# AJH_Wasp_1_02.net
KiCad netlist of a schematic drawn in EAGLE
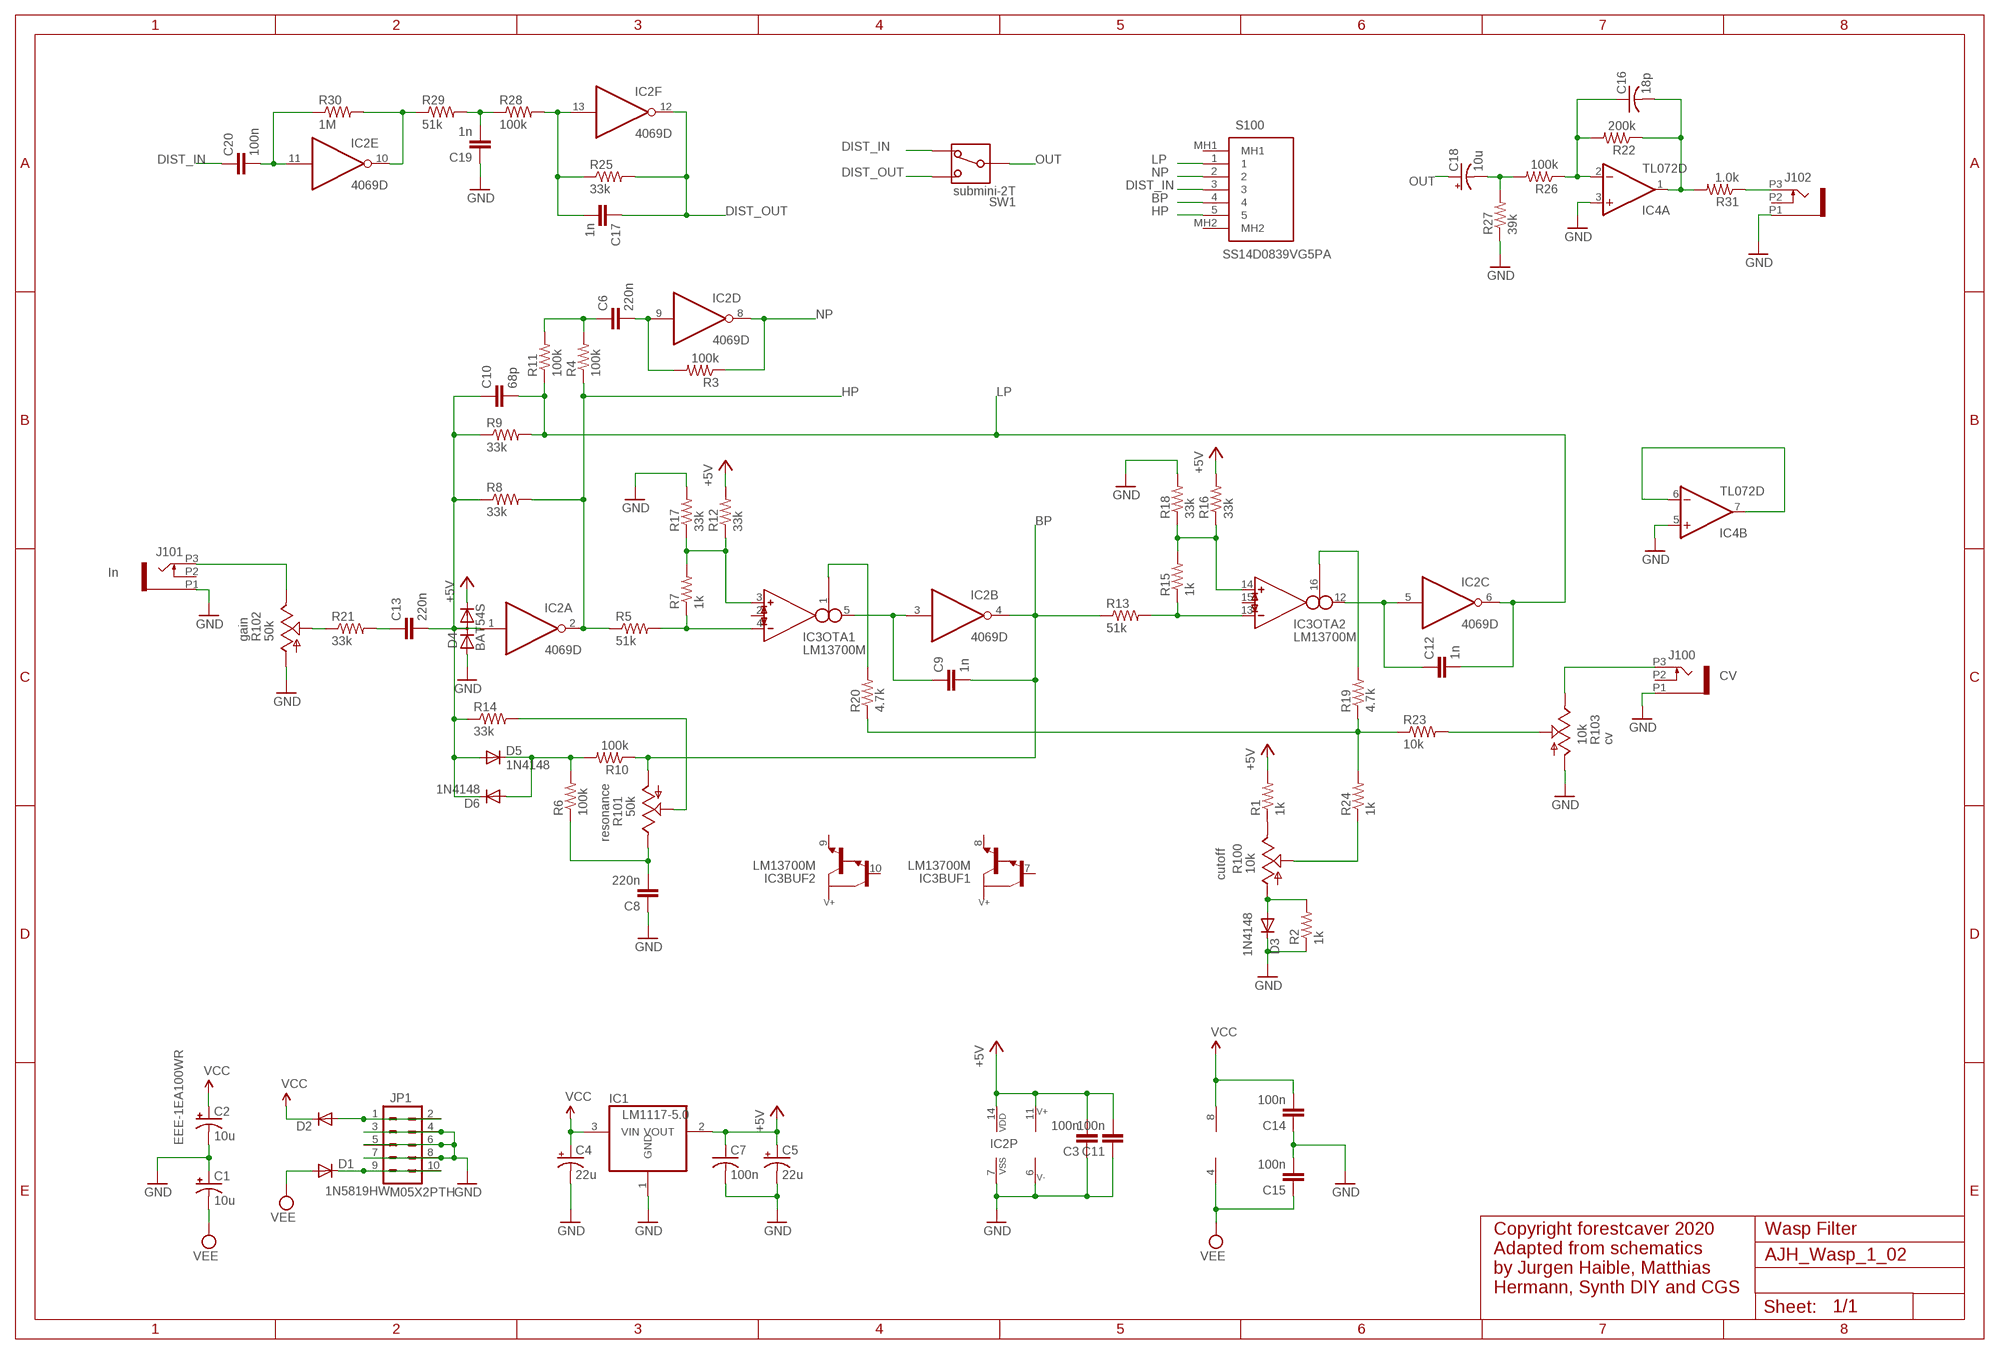
[diagram p0: schematic, sheet 1]

(export (version "E")
  (design (tool "Eeschema 10.0.6"))
  (components
    (comp (ref "C1")
      (value "10u")
      (footprint "eagle-import:PANASONIC_B")
      (libsource (lib "eagle-import") (part "CPOL-USB"))
    )
    (comp (ref "C2")
      (value "10u")
      (footprint "eagle-import:PANASONIC_B")
      (libsource (lib "eagle-import") (part "CPOL-USB"))
    )
    (comp (ref "C3")
      (value "100n")
      (footprint "eagle-import:C0603")
      (libsource (lib "eagle-import") (part "C-EUC0603"))
    )
    (comp (ref "C4")
      (value "22u")
      (footprint "eagle-import:PANASONIC_C")
      (libsource (lib "eagle-import") (part "CPOL-USC"))
    )
    (comp (ref "C5")
      (value "22u")
      (footprint "eagle-import:PANASONIC_C")
      (libsource (lib "eagle-import") (part "CPOL-USC"))
    )
    (comp (ref "C6")
      (value "220n")
      (footprint "eagle-import:C0603")
      (libsource (lib "eagle-import") (part "C-EUC0603"))
    )
    (comp (ref "C7")
      (value "100n")
      (footprint "eagle-import:C0603")
      (libsource (lib "eagle-import") (part "C-USC0603"))
    )
    (comp (ref "C8")
      (value "220n")
      (footprint "eagle-import:C0603")
      (libsource (lib "eagle-import") (part "C-EUC0603"))
    )
    (comp (ref "C9")
      (value "1n")
      (footprint "eagle-import:C0603")
      (libsource (lib "eagle-import") (part "C-EUC0603"))
    )
    (comp (ref "C10")
      (value "68p")
      (footprint "eagle-import:C0603")
      (libsource (lib "eagle-import") (part "C-EUC0603"))
    )
    (comp (ref "C11")
      (value "100n")
      (footprint "eagle-import:C0603")
      (libsource (lib "eagle-import") (part "C-EUC0603"))
    )
    (comp (ref "C12")
      (value "1n")
      (footprint "eagle-import:C0603")
      (libsource (lib "eagle-import") (part "C-EUC0603"))
    )
    (comp (ref "C13")
      (value "220n")
      (footprint "eagle-import:C0603")
      (libsource (lib "eagle-import") (part "C-EUC0603"))
    )
    (comp (ref "C14")
      (value "100n")
      (footprint "eagle-import:C0603")
      (libsource (lib "eagle-import") (part "C-EUC0603"))
    )
    (comp (ref "C15")
      (value "100n")
      (footprint "eagle-import:C0603")
      (libsource (lib "eagle-import") (part "C-EUC0603"))
    )
    (comp (ref "C16")
      (value "18p")
      (footprint "eagle-import:C0603")
      (libsource (lib "eagle-import") (part "C-USC0603"))
    )
    (comp (ref "C17")
      (value "1n")
      (footprint "eagle-import:C0603")
      (libsource (lib "eagle-import") (part "C-EUC0603"))
    )
    (comp (ref "C18")
      (value "10u")
      (footprint "eagle-import:PANASONIC_B")
      (libsource (lib "eagle-import") (part "CPOL-USB"))
    )
    (comp (ref "C19")
      (value "1n")
      (footprint "eagle-import:C0603")
      (libsource (lib "eagle-import") (part "C-EUC0603"))
    )
    (comp (ref "C20")
      (value "100n")
      (footprint "eagle-import:C0603")
      (libsource (lib "eagle-import") (part "C-EUC0603"))
    )
    (comp (ref "D1")
      (value "1N5819HW")
      (footprint "eagle-import:SOD123")
      (libsource (lib "eagle-import") (part "DIODE-SOD123"))
    )
    (comp (ref "D2")
      (value "1N5819HW")
      (footprint "eagle-import:SOD123")
      (libsource (lib "eagle-import") (part "DIODE-SOD123"))
    )
    (comp (ref "D3")
      (value "1N4148")
      (footprint "eagle-import:SOD523")
      (libsource (lib "eagle-import") (part "DIODE-SOD523"))
    )
    (comp (ref "D4")
      (value "BAT54S")
      (footprint "eagle-import:SOT23")
      (libsource (lib "eagle-import") (part "DIODE_2CACA-SOT23"))
    )
    (comp (ref "D5")
      (value "1N4148")
      (footprint "eagle-import:SOD523")
      (libsource (lib "eagle-import") (part "DIODE-SOD523"))
    )
    (comp (ref "D6")
      (value "1N4148")
      (footprint "eagle-import:SOD523")
      (libsource (lib "eagle-import") (part "DIODE-SOD523"))
    )
    (comp (ref "IC1")
      (value "LM1117-5.0")
      (footprint "eagle-import:SOT223")
      (libsource (lib "eagle-import") (part "REG1117"))
    )
    (comp (ref "IC2")
      (value "4069D")
      (footprint "eagle-import:SO14")
      (libsource (lib "eagle-import") (part "4069D"))
    )
    (comp (ref "IC3")
      (value "LM13700M")
      (footprint "eagle-import:SO16")
      (libsource (lib "eagle-import") (part "LM13700M"))
    )
    (comp (ref "IC4")
      (value "TL072D")
      (footprint "eagle-import:SO08")
      (libsource (lib "eagle-import") (part "TL072D"))
    )
    (comp (ref "J100")
      (value "PJ301_THONKICONN8")
      (footprint "eagle-import:WQP_PJ_301M8")
      (fields (field (name "LABEL") "CV"))
      (libsource (lib "eagle-import") (part "PJ301_THONKICONN8"))
    )
    (comp (ref "J101")
      (value "PJ301_THONKICONN8")
      (footprint "eagle-import:WQP_PJ_301M8")
      (fields (field (name "LABEL") "In"))
      (libsource (lib "eagle-import") (part "PJ301_THONKICONN8"))
    )
    (comp (ref "J102")
      (value "PJ301_THONKICONN6")
      (footprint "eagle-import:WQP_PJ_301M6")
      (libsource (lib "eagle-import") (part "PJ301_THONKICONN6"))
    )
    (comp (ref "JP1")
      (value "M05X2PTH")
      (footprint "eagle-import:AVR_ICSP")
      (libsource (lib "eagle-import") (part "M05X2PTH"))
    )
    (comp (ref "R1")
      (value "1k")
      (footprint "eagle-import:R0603")
      (libsource (lib "eagle-import") (part "rcl_334_R-US_R0603"))
    )
    (comp (ref "R2")
      (value "1k")
      (footprint "eagle-import:R0603")
      (libsource (lib "eagle-import") (part "rcl_334_R-US_R0603"))
    )
    (comp (ref "R3")
      (value "100k")
      (footprint "eagle-import:R0603")
      (libsource (lib "eagle-import") (part "rcl_334_R-US_R0603"))
    )
    (comp (ref "R4")
      (value "100k")
      (footprint "eagle-import:R0603")
      (libsource (lib "eagle-import") (part "rcl_334_R-US_R0603"))
    )
    (comp (ref "R5")
      (value "51k")
      (footprint "eagle-import:R0603")
      (libsource (lib "eagle-import") (part "rcl_334_R-US_R0603"))
    )
    (comp (ref "R6")
      (value "100k")
      (footprint "eagle-import:R0603")
      (libsource (lib "eagle-import") (part "rcl_334_R-US_R0603"))
    )
    (comp (ref "R7")
      (value "1k")
      (footprint "eagle-import:R0603")
      (libsource (lib "eagle-import") (part "rcl_334_R-US_R0603"))
    )
    (comp (ref "R8")
      (value "33k")
      (footprint "eagle-import:R0603")
      (libsource (lib "eagle-import") (part "rcl_334_R-US_R0603"))
    )
    (comp (ref "R9")
      (value "33k")
      (footprint "eagle-import:R0603")
      (libsource (lib "eagle-import") (part "rcl_334_R-US_R0603"))
    )
    (comp (ref "R10")
      (value "100k")
      (footprint "eagle-import:R0603")
      (libsource (lib "eagle-import") (part "rcl_334_R-US_R0603"))
    )
    (comp (ref "R11")
      (value "100k")
      (footprint "eagle-import:R0603")
      (libsource (lib "eagle-import") (part "rcl_334_R-US_R0603"))
    )
    (comp (ref "R12")
      (value "33k")
      (footprint "eagle-import:R0603")
      (libsource (lib "eagle-import") (part "rcl_334_R-US_R0603"))
    )
    (comp (ref "R13")
      (value "51k")
      (footprint "eagle-import:R0603")
      (libsource (lib "eagle-import") (part "rcl_334_R-US_R0603"))
    )
    (comp (ref "R14")
      (value "33k")
      (footprint "eagle-import:R0603")
      (libsource (lib "eagle-import") (part "rcl_334_R-US_R0603"))
    )
    (comp (ref "R15")
      (value "1k")
      (footprint "eagle-import:R0603")
      (libsource (lib "eagle-import") (part "rcl_334_R-US_R0603"))
    )
    (comp (ref "R16")
      (value "33k")
      (footprint "eagle-import:R0603")
      (libsource (lib "eagle-import") (part "rcl_334_R-US_R0603"))
    )
    (comp (ref "R17")
      (value "33k")
      (footprint "eagle-import:R0603")
      (libsource (lib "eagle-import") (part "rcl_334_R-US_R0603"))
    )
    (comp (ref "R18")
      (value "33k")
      (footprint "eagle-import:R0603")
      (libsource (lib "eagle-import") (part "rcl_334_R-US_R0603"))
    )
    (comp (ref "R19")
      (value "4.7k")
      (footprint "eagle-import:R0603")
      (libsource (lib "eagle-import") (part "rcl_334_R-US_R0603"))
    )
    (comp (ref "R20")
      (value "4.7k")
      (footprint "eagle-import:R0603")
      (libsource (lib "eagle-import") (part "rcl_334_R-US_R0603"))
    )
    (comp (ref "R21")
      (value "33k")
      (footprint "eagle-import:R0603")
      (libsource (lib "eagle-import") (part "rcl_334_R-US_R0603"))
    )
    (comp (ref "R22")
      (value "200k")
      (footprint "eagle-import:R0603")
      (libsource (lib "eagle-import") (part "R-US_R0603"))
    )
    (comp (ref "R23")
      (value "10k")
      (footprint "eagle-import:R0603")
      (libsource (lib "eagle-import") (part "rcl_334_R-US_R0603"))
    )
    (comp (ref "R24")
      (value "1k")
      (footprint "eagle-import:R0603")
      (libsource (lib "eagle-import") (part "rcl_334_R-US_R0603"))
    )
    (comp (ref "R25")
      (value "33k")
      (footprint "eagle-import:R0603")
      (libsource (lib "eagle-import") (part "rcl_334_R-US_R0603"))
    )
    (comp (ref "R26")
      (value "100k")
      (footprint "eagle-import:R0603")
      (libsource (lib "eagle-import") (part "R-US_R0603"))
    )
    (comp (ref "R27")
      (value "39k")
      (footprint "eagle-import:R0603")
      (libsource (lib "eagle-import") (part "R-US_R0603"))
    )
    (comp (ref "R28")
      (value "100k")
      (footprint "eagle-import:R0603")
      (libsource (lib "eagle-import") (part "rcl_334_R-US_R0603"))
    )
    (comp (ref "R29")
      (value "51k")
      (footprint "eagle-import:R0603")
      (libsource (lib "eagle-import") (part "rcl_334_R-US_R0603"))
    )
    (comp (ref "R30")
      (value "1M")
      (footprint "eagle-import:R0603")
      (libsource (lib "eagle-import") (part "rcl_334_R-US_R0603"))
    )
    (comp (ref "R31")
      (value "1.0k")
      (footprint "eagle-import:R0603")
      (libsource (lib "eagle-import") (part "R-US_R0603"))
    )
    (comp (ref "R100")
      (value "10k")
      (footprint "eagle-import:ALPS_POT_VERTICAL_PS")
      (fields (field (name "LABEL") "cutoff"))
      (libsource (lib "eagle-import") (part "POT_USVERTICAL_PS"))
    )
    (comp (ref "R101")
      (value "50k")
      (footprint "eagle-import:ALPS_POT_VERTICAL_PS")
      (fields (field (name "LABEL") "resonance"))
      (libsource (lib "eagle-import") (part "POT_USVERTICAL_PS"))
    )
    (comp (ref "R102")
      (value "50k")
      (footprint "eagle-import:ALPS_POT_VERTICAL_PS")
      (fields (field (name "LABEL") "gain"))
      (libsource (lib "eagle-import") (part "POT_USVERTICAL_PS"))
    )
    (comp (ref "R103")
      (value "10k")
      (footprint "eagle-import:ALPS_POT_VERTICAL_PS")
      (fields (field (name "LABEL") "cv"))
      (libsource (lib "eagle-import") (part "POT_USVERTICAL_PS"))
    )
    (comp (ref "S100")
      (value "SS14D0839VG5PA")
      (footprint "eagle-import:SS14D0839VG5PA")
      (fields (field (name "MOUSER_PART_NUMBER") "611-SS-14D0839-VG5PA"))
      (libsource (lib "eagle-import") (part "SS14D0839VG5PA"))
    )
    (comp (ref "SW1")
      (value "submini-2T")
      (footprint "eagle-import:SPDT-SUB")
      (libsource (lib "eagle-import") (part "SPDTT"))
    )
  )
  (nets
    (net (code "1") (name "+5V") (class "Default")
      (node (ref "C11") (pin "2") (pinfunction "2_2") (pintype "passive"))
      (node (ref "C3") (pin "2") (pinfunction "2_2") (pintype "passive"))
      (node (ref "C5") (pin "+") (pinfunction "+_+") (pintype "passive"))
      (node (ref "C7") (pin "1") (pinfunction "1_1") (pintype "passive"))
      (node (ref "D4") (pin "2") (pinfunction "C_2") (pintype "passive"))
      (node (ref "IC1") (pin "2") (pinfunction "VOUT_2") (pintype "output"))
      (node (ref "IC2") (pin "14") (pinfunction "VDD_14") (pintype "power_in"))
      (node (ref "IC3") (pin "11") (pinfunction "V+_11") (pintype "power_in"))
      (node (ref "R1") (pin "2") (pinfunction "2_2") (pintype "passive"))
      (node (ref "R12") (pin "2") (pinfunction "2_2") (pintype "passive"))
      (node (ref "R16") (pin "2") (pinfunction "2_2") (pintype "passive"))
    )
    (net (code "2") (name "/BP") (class "Default")
      (node (ref "C9") (pin "2") (pinfunction "2_2") (pintype "passive"))
      (node (ref "IC2") (pin "4") (pinfunction "O_4") (pintype "output"))
      (node (ref "R10") (pin "1") (pinfunction "1_1") (pintype "passive"))
      (node (ref "R101") (pin "P$3") (pinfunction "A_P$3") (pintype "passive"))
      (node (ref "R13") (pin "1") (pinfunction "1_1") (pintype "passive"))
      (node (ref "S100") (pin "4") (pinfunction "4_4") (pintype "bidirectional"))
    )
    (net (code "3") (name "/DIST_IN") (class "Default")
      (node (ref "C20") (pin "1") (pinfunction "1_1") (pintype "passive"))
      (node (ref "S100") (pin "3") (pinfunction "3_3") (pintype "bidirectional"))
      (node (ref "SW1") (pin "P$3") (pinfunction "P$3_P$3") (pintype "passive"))
    )
    (net (code "4") (name "/DIST_OUT") (class "Default")
      (node (ref "C17") (pin "1") (pinfunction "1_1") (pintype "passive"))
      (node (ref "IC2") (pin "12") (pinfunction "O_12") (pintype "output"))
      (node (ref "R25") (pin "2") (pinfunction "2_2") (pintype "passive"))
      (node (ref "SW1") (pin "P$1") (pinfunction "P$1_P$1") (pintype "passive"))
    )
    (net (code "5") (name "/HP") (class "Default")
      (node (ref "IC2") (pin "2") (pinfunction "O_2") (pintype "output"))
      (node (ref "R4") (pin "1") (pinfunction "1_1") (pintype "passive"))
      (node (ref "R5") (pin "1") (pinfunction "1_1") (pintype "passive"))
      (node (ref "R8") (pin "2") (pinfunction "2_2") (pintype "passive"))
      (node (ref "S100") (pin "5") (pinfunction "5_5") (pintype "bidirectional"))
    )
    (net (code "6") (name "/LP") (class "Default")
      (node (ref "C10") (pin "2") (pinfunction "2_2") (pintype "passive"))
      (node (ref "C12") (pin "2") (pinfunction "2_2") (pintype "passive"))
      (node (ref "IC2") (pin "6") (pinfunction "O_6") (pintype "output"))
      (node (ref "R11") (pin "1") (pinfunction "1_1") (pintype "passive"))
      (node (ref "R9") (pin "2") (pinfunction "2_2") (pintype "passive"))
      (node (ref "S100") (pin "1") (pinfunction "1_1") (pintype "bidirectional"))
    )
    (net (code "7") (name "/NP") (class "Default")
      (node (ref "IC2") (pin "8") (pinfunction "O_8") (pintype "output"))
      (node (ref "R3") (pin "1") (pinfunction "1_1") (pintype "passive"))
      (node (ref "S100") (pin "2") (pinfunction "2_2") (pintype "bidirectional"))
    )
    (net (code "8") (name "/OUT") (class "Default")
      (node (ref "C18") (pin "+") (pinfunction "+_+") (pintype "passive"))
      (node (ref "SW1") (pin "P$2") (pinfunction "P$2_P$2") (pintype "passive"))
    )
    (net (code "9") (name "GND") (class "Default")
      (node (ref "C1") (pin "+") (pinfunction "+_+") (pintype "passive"))
      (node (ref "C11") (pin "1") (pinfunction "1_1") (pintype "passive"))
      (node (ref "C14") (pin "1") (pinfunction "1_1") (pintype "passive"))
      (node (ref "C15") (pin "2") (pinfunction "2_2") (pintype "passive"))
      (node (ref "C19") (pin "1") (pinfunction "1_1") (pintype "passive"))
      (node (ref "C2") (pin "-") (pinfunction "-_-") (pintype "passive"))
      (node (ref "C3") (pin "1") (pinfunction "1_1") (pintype "passive"))
      (node (ref "C4") (pin "-") (pinfunction "-_-") (pintype "passive"))
      (node (ref "C5") (pin "-") (pinfunction "-_-") (pintype "passive"))
      (node (ref "C7") (pin "2") (pinfunction "2_2") (pintype "passive"))
      (node (ref "C8") (pin "1") (pinfunction "1_1") (pintype "passive"))
      (node (ref "D3") (pin "C") (pinfunction "C_C") (pintype "passive"))
      (node (ref "D4") (pin "1") (pinfunction "A_1") (pintype "passive"))
      (node (ref "IC1") (pin "1") (pinfunction "GND_1") (pintype "power_in"))
      (node (ref "IC2") (pin "7") (pinfunction "VSS_7") (pintype "power_in"))
      (node (ref "IC3") (pin "6") (pinfunction "V-_6") (pintype "power_in"))
      (node (ref "IC4") (pin "3") (pinfunction "+IN_3") (pintype "input"))
      (node (ref "IC4") (pin "5") (pinfunction "+IN_5") (pintype "input"))
      (node (ref "J100") (pin "P1") (pinfunction "1_P1") (pintype "passive"))
      (node (ref "J101") (pin "P1") (pinfunction "1_P1") (pintype "passive"))
      (node (ref "J102") (pin "P1") (pinfunction "1_P1") (pintype "passive"))
      (node (ref "JP1") (pin "3") (pinfunction "3_3") (pintype "passive"))
      (node (ref "JP1") (pin "4") (pinfunction "4_4") (pintype "passive"))
      (node (ref "JP1") (pin "5") (pinfunction "5_5") (pintype "passive"))
      (node (ref "JP1") (pin "6") (pinfunction "6_6") (pintype "passive"))
      (node (ref "JP1") (pin "7") (pinfunction "7_7") (pintype "passive"))
      (node (ref "JP1") (pin "8") (pinfunction "8_8") (pintype "passive"))
      (node (ref "R102") (pin "P$3") (pinfunction "A_P$3") (pintype "passive"))
      (node (ref "R103") (pin "P$3") (pinfunction "A_P$3") (pintype "passive"))
      (node (ref "R17") (pin "2") (pinfunction "2_2") (pintype "passive"))
      (node (ref "R18") (pin "2") (pinfunction "2_2") (pintype "passive"))
      (node (ref "R2") (pin "1") (pinfunction "1_1") (pintype "passive"))
      (node (ref "R27") (pin "1") (pinfunction "1_1") (pintype "passive"))
    )
    (net (code "10") (name "Net-(C6-Pad1)") (class "Default")
      (node (ref "C6") (pin "1") (pinfunction "1_1") (pintype "passive"))
      (node (ref "R11") (pin "2") (pinfunction "2_2") (pintype "passive"))
      (node (ref "R4") (pin "2") (pinfunction "2_2") (pintype "passive"))
    )
    (net (code "11") (name "Net-(C13-Pad1)") (class "Default")
      (node (ref "C13") (pin "1") (pinfunction "1_1") (pintype "passive"))
      (node (ref "R21") (pin "2") (pinfunction "2_2") (pintype "passive"))
    )
    (net (code "12") (name "Net-(C18-Pad-)") (class "Default")
      (node (ref "C18") (pin "-") (pinfunction "-_-") (pintype "passive"))
      (node (ref "R26") (pin "2") (pinfunction "2_2") (pintype "passive"))
      (node (ref "R27") (pin "2") (pinfunction "2_2") (pintype "passive"))
    )
    (net (code "13") (name "Net-(C19-Pad2)") (class "Default")
      (node (ref "C19") (pin "2") (pinfunction "2_2") (pintype "passive"))
      (node (ref "R28") (pin "1") (pinfunction "1_1") (pintype "passive"))
      (node (ref "R29") (pin "2") (pinfunction "2_2") (pintype "passive"))
    )
    (net (code "14") (name "Net-(D1-PadC)") (class "Default")
      (node (ref "D1") (pin "C") (pinfunction "C_C") (pintype "passive"))
      (node (ref "JP1") (pin "10") (pinfunction "10_10") (pintype "passive"))
      (node (ref "JP1") (pin "9") (pinfunction "9_9") (pintype "passive"))
    )
    (net (code "15") (name "Net-(D2-PadA)") (class "Default")
      (node (ref "D2") (pin "A") (pinfunction "A_A") (pintype "passive"))
      (node (ref "JP1") (pin "1") (pinfunction "1_1") (pintype "passive"))
      (node (ref "JP1") (pin "2") (pinfunction "2_2") (pintype "passive"))
    )
    (net (code "16") (name "Net-(D4-AC)") (class "Default")
      (node (ref "C10") (pin "1") (pinfunction "1_1") (pintype "passive"))
      (node (ref "C13") (pin "2") (pinfunction "2_2") (pintype "passive"))
      (node (ref "D4") (pin "3") (pinfunction "AC_3") (pintype "passive"))
      (node (ref "D5") (pin "A") (pinfunction "A_A") (pintype "passive"))
      (node (ref "D6") (pin "C") (pinfunction "C_C") (pintype "passive"))
      (node (ref "IC2") (pin "1") (pinfunction "I_1") (pintype "input"))
      (node (ref "R14") (pin "1") (pinfunction "1_1") (pintype "passive"))
      (node (ref "R8") (pin "1") (pinfunction "1_1") (pintype "passive"))
      (node (ref "R9") (pin "1") (pinfunction "1_1") (pintype "passive"))
    )
    (net (code "17") (name "Net-(D5-PadC)") (class "Default")
      (node (ref "D5") (pin "C") (pinfunction "C_C") (pintype "passive"))
      (node (ref "D6") (pin "A") (pinfunction "A_A") (pintype "passive"))
      (node (ref "R10") (pin "2") (pinfunction "2_2") (pintype "passive"))
      (node (ref "R6") (pin "2") (pinfunction "2_2") (pintype "passive"))
    )
    (net (code "18") (name "Net-(IC2B-I)") (class "Default")
      (node (ref "C9") (pin "1") (pinfunction "1_1") (pintype "passive"))
      (node (ref "IC2") (pin "3") (pinfunction "I_3") (pintype "input"))
      (node (ref "IC3") (pin "5") (pinfunction "OUT_5") (pintype "output"))
    )
    (net (code "19") (name "Net-(IC2C-I)") (class "Default")
      (node (ref "C12") (pin "1") (pinfunction "1_1") (pintype "passive"))
      (node (ref "IC2") (pin "5") (pinfunction "I_5") (pintype "input"))
      (node (ref "IC3") (pin "12") (pinfunction "OUT_12") (pintype "output"))
    )
    (net (code "20") (name "Net-(IC2D-I)") (class "Default")
      (node (ref "C6") (pin "2") (pinfunction "2_2") (pintype "passive"))
      (node (ref "IC2") (pin "9") (pinfunction "I_9") (pintype "input"))
      (node (ref "R3") (pin "2") (pinfunction "2_2") (pintype "passive"))
    )
    (net (code "21") (name "Net-(IC2E-I)") (class "Default")
      (node (ref "C20") (pin "2") (pinfunction "2_2") (pintype "passive"))
      (node (ref "IC2") (pin "11") (pinfunction "I_11") (pintype "input"))
      (node (ref "R30") (pin "1") (pinfunction "1_1") (pintype "passive"))
    )
    (net (code "22") (name "Net-(IC2E-O)") (class "Default")
      (node (ref "IC2") (pin "10") (pinfunction "O_10") (pintype "output"))
      (node (ref "R29") (pin "1") (pinfunction "1_1") (pintype "passive"))
      (node (ref "R30") (pin "2") (pinfunction "2_2") (pintype "passive"))
    )
    (net (code "23") (name "Net-(IC2F-I)") (class "Default")
      (node (ref "C17") (pin "2") (pinfunction "2_2") (pintype "passive"))
      (node (ref "IC2") (pin "13") (pinfunction "I_13") (pintype "input"))
      (node (ref "R25") (pin "1") (pinfunction "1_1") (pintype "passive"))
      (node (ref "R28") (pin "2") (pinfunction "2_2") (pintype "passive"))
    )
    (net (code "24") (name "Net-(IC3C-IN_N)") (class "Default")
      (node (ref "IC3") (pin "4") (pinfunction "IN_N_4") (pintype "input"))
      (node (ref "R5") (pin "2") (pinfunction "2_2") (pintype "passive"))
      (node (ref "R7") (pin "1") (pinfunction "1_1") (pintype "passive"))
    )
    (net (code "25") (name "Net-(IC3C-IN_P)") (class "Default")
      (node (ref "IC3") (pin "3") (pinfunction "IN_P_3") (pintype "input"))
      (node (ref "R12") (pin "1") (pinfunction "1_1") (pintype "passive"))
      (node (ref "R17") (pin "1") (pinfunction "1_1") (pintype "passive"))
      (node (ref "R7") (pin "2") (pinfunction "2_2") (pintype "passive"))
    )
    (net (code "26") (name "Net-(IC3C-I_BIAS)") (class "Default")
      (node (ref "IC3") (pin "1") (pinfunction "I_BIAS_1") (pintype "input"))
      (node (ref "R20") (pin "2") (pinfunction "2_2") (pintype "passive"))
    )
    (net (code "27") (name "Net-(IC3D-IN_N)") (class "Default")
      (node (ref "IC3") (pin "13") (pinfunction "IN_N_13") (pintype "input"))
      (node (ref "R13") (pin "2") (pinfunction "2_2") (pintype "passive"))
      (node (ref "R15") (pin "1") (pinfunction "1_1") (pintype "passive"))
    )
    (net (code "28") (name "Net-(IC3D-IN_P)") (class "Default")
      (node (ref "IC3") (pin "14") (pinfunction "IN_P_14") (pintype "input"))
      (node (ref "R15") (pin "2") (pinfunction "2_2") (pintype "passive"))
      (node (ref "R16") (pin "1") (pinfunction "1_1") (pintype "passive"))
      (node (ref "R18") (pin "1") (pinfunction "1_1") (pintype "passive"))
    )
    (net (code "29") (name "Net-(IC3D-I_BIAS)") (class "Default")
      (node (ref "IC3") (pin "16") (pinfunction "I_BIAS_16") (pintype "input"))
      (node (ref "R19") (pin "2") (pinfunction "2_2") (pintype "passive"))
    )
    (net (code "30") (name "Net-(IC4A--IN)") (class "Default")
      (node (ref "C16") (pin "1") (pinfunction "1_1") (pintype "passive"))
      (node (ref "IC4") (pin "2") (pinfunction "-IN_2") (pintype "input"))
      (node (ref "R22") (pin "2") (pinfunction "2_2") (pintype "passive"))
      (node (ref "R26") (pin "1") (pinfunction "1_1") (pintype "passive"))
    )
    (net (code "31") (name "Net-(IC4A-OUT)") (class "Default")
      (node (ref "C16") (pin "2") (pinfunction "2_2") (pintype "passive"))
      (node (ref "IC4") (pin "1") (pinfunction "OUT_1") (pintype "output"))
      (node (ref "R22") (pin "1") (pinfunction "1_1") (pintype "passive"))
      (node (ref "R31") (pin "2") (pinfunction "2_2") (pintype "passive"))
    )
    (net (code "32") (name "Net-(IC4B--IN)") (class "Default")
      (node (ref "IC4") (pin "6") (pinfunction "-IN_6") (pintype "input"))
      (node (ref "IC4") (pin "7") (pinfunction "OUT_7") (pintype "output"))
    )
    (net (code "33") (name "Net-(J100-3)") (class "Default")
      (node (ref "J100") (pin "P3") (pinfunction "3_P3") (pintype "passive"))
      (node (ref "R103") (pin "P$1") (pinfunction "E_P$1") (pintype "passive"))
    )
    (net (code "34") (name "Net-(J101-3)") (class "Default")
      (node (ref "J101") (pin "P3") (pinfunction "3_P3") (pintype "passive"))
      (node (ref "R102") (pin "P$1") (pinfunction "E_P$1") (pintype "passive"))
    )
    (net (code "35") (name "Net-(J102-3)") (class "Default")
      (node (ref "J102") (pin "P3") (pinfunction "3_P3") (pintype "passive"))
      (node (ref "R31") (pin "1") (pinfunction "1_1") (pintype "passive"))
    )
    (net (code "36") (name "Net-(R19-Pad1)") (class "Default")
      (node (ref "R19") (pin "1") (pinfunction "1_1") (pintype "passive"))
      (node (ref "R20") (pin "1") (pinfunction "1_1") (pintype "passive"))
      (node (ref "R23") (pin "1") (pinfunction "1_1") (pintype "passive"))
      (node (ref "R24") (pin "2") (pinfunction "2_2") (pintype "passive"))
    )
    (net (code "37") (name "Net-(R100-A)") (class "Default")
      (node (ref "D3") (pin "A") (pinfunction "A_A") (pintype "passive"))
      (node (ref "R100") (pin "P$3") (pinfunction "A_P$3") (pintype "passive"))
      (node (ref "R2") (pin "2") (pinfunction "2_2") (pintype "passive"))
    )
    (net (code "38") (name "Net-(R100-E)") (class "Default")
      (node (ref "R1") (pin "1") (pinfunction "1_1") (pintype "passive"))
      (node (ref "R100") (pin "P$1") (pinfunction "E_P$1") (pintype "passive"))
    )
    (net (code "39") (name "Net-(R100-S)") (class "Default")
      (node (ref "R100") (pin "P$2") (pinfunction "S_P$2") (pintype "passive"))
      (node (ref "R24") (pin "1") (pinfunction "1_1") (pintype "passive"))
    )
    (net (code "40") (name "Net-(R101-E)") (class "Default")
      (node (ref "C8") (pin "2") (pinfunction "2_2") (pintype "passive"))
      (node (ref "R101") (pin "P$1") (pinfunction "E_P$1") (pintype "passive"))
      (node (ref "R6") (pin "1") (pinfunction "1_1") (pintype "passive"))
    )
    (net (code "41") (name "Net-(R101-S)") (class "Default")
      (node (ref "R101") (pin "P$2") (pinfunction "S_P$2") (pintype "passive"))
      (node (ref "R14") (pin "2") (pinfunction "2_2") (pintype "passive"))
    )
    (net (code "42") (name "Net-(R102-S)") (class "Default")
      (node (ref "R102") (pin "P$2") (pinfunction "S_P$2") (pintype "passive"))
      (node (ref "R21") (pin "1") (pinfunction "1_1") (pintype "passive"))
    )
    (net (code "43") (name "Net-(R103-S)") (class "Default")
      (node (ref "R103") (pin "P$2") (pinfunction "S_P$2") (pintype "passive"))
      (node (ref "R23") (pin "2") (pinfunction "2_2") (pintype "passive"))
    )
    (net (code "44") (name "VCC") (class "Default")
      (node (ref "C14") (pin "2") (pinfunction "2_2") (pintype "passive"))
      (node (ref "C2") (pin "+") (pinfunction "+_+") (pintype "passive"))
      (node (ref "C4") (pin "+") (pinfunction "+_+") (pintype "passive"))
      (node (ref "D2") (pin "C") (pinfunction "C_C") (pintype "passive"))
      (node (ref "IC1") (pin "3") (pinfunction "VIN_3") (pintype "input"))
      (node (ref "IC4") (pin "8") (pinfunction "V+_8") (pintype "power_in"))
    )
    (net (code "45") (name "VEE") (class "Default")
      (node (ref "C1") (pin "-") (pinfunction "-_-") (pintype "passive"))
      (node (ref "C15") (pin "1") (pinfunction "1_1") (pintype "passive"))
      (node (ref "D1") (pin "A") (pinfunction "A_A") (pintype "passive"))
      (node (ref "IC4") (pin "4") (pinfunction "V-_4") (pintype "power_in"))
    )
    (net (code "46") (name "unconnected-(IC3A-B-Pad7)") (class "Default")
      (node (ref "IC3") (pin "7") (pinfunction "B_7") (pintype "passive"))
    )
    (net (code "47") (name "unconnected-(IC3A-E-Pad8)") (class "Default")
      (node (ref "IC3") (pin "8") (pinfunction "E_8") (pintype "passive"))
    )
    (net (code "48") (name "unconnected-(IC3B-B-Pad10)") (class "Default")
      (node (ref "IC3") (pin "10") (pinfunction "B_10") (pintype "passive"))
    )
    (net (code "49") (name "unconnected-(IC3B-E-Pad9)") (class "Default")
      (node (ref "IC3") (pin "9") (pinfunction "E_9") (pintype "passive"))
    )
    (net (code "50") (name "unconnected-(IC3C-I_DIODE-Pad2)") (class "Default")
      (node (ref "IC3") (pin "2") (pinfunction "I_DIODE_2") (pintype "input"))
    )
    (net (code "51") (name "unconnected-(IC3D-I_DIODE-Pad15)") (class "Default")
      (node (ref "IC3") (pin "15") (pinfunction "I_DIODE_15") (pintype "input"))
    )
    (net (code "52") (name "unconnected-(J100-2-PadP2)") (class "Default")
      (node (ref "J100") (pin "P2") (pinfunction "2_P2") (pintype "passive"))
    )
    (net (code "53") (name "unconnected-(J101-2-PadP2)") (class "Default")
      (node (ref "J101") (pin "P2") (pinfunction "2_P2") (pintype "passive"))
    )
    (net (code "54") (name "unconnected-(J102-2-PadP2)") (class "Default")
      (node (ref "J102") (pin "P2") (pinfunction "2_P2") (pintype "passive"))
    )
    (net (code "55") (name "unconnected-(S100-PadMH1)") (class "Default")
      (node (ref "S100") (pin "MH1") (pinfunction "MH1_MH1") (pintype "bidirectional"))
    )
    (net (code "56") (name "unconnected-(S100-PadMH2)") (class "Default")
      (node (ref "S100") (pin "MH2") (pinfunction "MH2_MH2") (pintype "bidirectional"))
    )
  )
)
